# Power.net
KiCad netlist of a schematic drawn in EAGLE
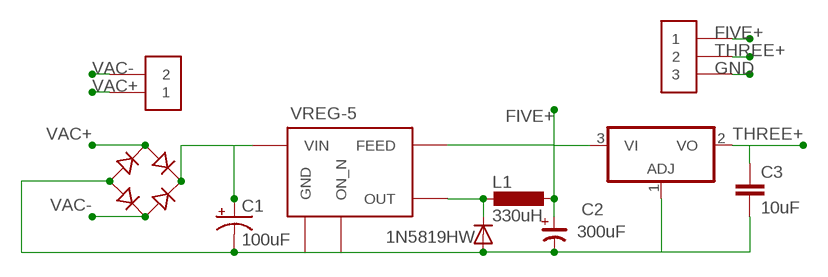
[diagram p0: schematic, sheet 1]

(export (version "E")
  (design (tool "Eeschema 10.0.6"))
  (components
    (comp (ref "B1")
      (value "RECTIFIER-S80")
      (footprint "eagle-import:TO-269AA")
      (libsource (lib "eagle-import") (part "RECTIFIER-S80"))
    )
    (comp (ref "C1")
      (value "100uF")
      (footprint "eagle-import:PANASONIC_G")
      (libsource (lib "eagle-import") (part "CPOL-USG"))
    )
    (comp (ref "C2")
      (value "300uF")
      (footprint "eagle-import:CSV-H")
      (libsource (lib "eagle-import") (part "CP_SV-H"))
    )
    (comp (ref "C3")
      (value "10uF")
      (footprint "eagle-import:C5B2.5")
      (libsource (lib "eagle-import") (part "C5/2.5"))
    )
    (comp (ref "D8")
      (value "CGRM4001-G")
      (footprint "eagle-import:SOD-123_MINI-SMA")
      (libsource (lib "eagle-import") (part "CGRM400-G1"))
    )
    (comp (ref "L1")
      (value "330uH")
      (footprint "eagle-import:DO3316P")
      (libsource (lib "eagle-import") (part "DO3316P"))
    )
    (comp (ref "LT1086-3.3")
      (value "317T")
      (footprint "eagle-import:TO220H")
      (libsource (lib "eagle-import") (part "317T"))
    )
    (comp (ref "U$2")
      (value "OSTTC020162")
      (footprint "eagle-import:OSTTC020162")
      (libsource (lib "eagle-import") (part "OSTTC020162"))
    )
    (comp (ref "U$3")
      (value "OSTTC030162")
      (footprint "eagle-import:OSTTC030162")
      (libsource (lib "eagle-import") (part "OSTTC030162"))
    )
    (comp (ref "VREG-5")
      (value "TL2575-05")
      (footprint "eagle-import:TO-263-5")
      (libsource (lib "eagle-import") (part "TL2575-05"))
    )
  )
  (nets
    (net (code "1") (name "/FIVE+") (class "Default")
      (node (ref "C2") (pin "+") (pinfunction "+_+") (pintype "passive"))
      (node (ref "L1") (pin "2") (pinfunction "2_2") (pintype "passive"))
      (node (ref "LT1086-3.3") (pin "3") (pinfunction "VI_3") (pintype "input"))
      (node (ref "U$3") (pin "1") (pinfunction "1_1") (pintype "bidirectional"))
      (node (ref "VREG-5") (pin "4") (pinfunction "FEED_4") (pintype "bidirectional"))
    )
    (net (code "2") (name "/GND") (class "Default")
      (node (ref "B1") (pin "-") (pinfunction "-_-") (pintype "passive"))
      (node (ref "C1") (pin "-") (pinfunction "-_-") (pintype "passive"))
      (node (ref "C2") (pin "-") (pinfunction "-_-") (pintype "passive"))
      (node (ref "C3") (pin "2") (pinfunction "2_2") (pintype "passive"))
      (node (ref "D8") (pin "A") (pinfunction "A_A") (pintype "passive"))
      (node (ref "LT1086-3.3") (pin "1") (pinfunction "ADJ_1") (pintype "input"))
      (node (ref "U$3") (pin "3") (pinfunction "3_3") (pintype "bidirectional"))
      (node (ref "VREG-5") (pin "3") (pinfunction "GND_3") (pintype "bidirectional"))
      (node (ref "VREG-5") (pin "5") (pinfunction "ON_N_5") (pintype "bidirectional"))
      (node (ref "VREG-5") (pin "TAB") (pinfunction "GND_TAB") (pintype "bidirectional"))
    )
    (net (code "3") (name "/THREE+") (class "Default")
      (node (ref "C3") (pin "1") (pinfunction "1_1") (pintype "passive"))
      (node (ref "LT1086-3.3") (pin "2") (pinfunction "VO_2") (pintype "passive"))
      (node (ref "U$3") (pin "2") (pinfunction "2_2") (pintype "bidirectional"))
    )
    (net (code "4") (name "/VAC+") (class "Default")
      (node (ref "B1") (pin "AC1") (pinfunction "AC1_AC1") (pintype "passive"))
      (node (ref "U$2") (pin "1") (pinfunction "1_1") (pintype "bidirectional"))
    )
    (net (code "5") (name "/VAC-") (class "Default")
      (node (ref "B1") (pin "AC2") (pinfunction "AC2_AC2") (pintype "passive"))
      (node (ref "U$2") (pin "2") (pinfunction "2_2") (pintype "bidirectional"))
    )
    (net (code "6") (name "Net-(VREG-5-OUT)") (class "Default")
      (node (ref "D8") (pin "C") (pinfunction "C_C") (pintype "passive"))
      (node (ref "L1") (pin "1") (pinfunction "1_1") (pintype "passive"))
      (node (ref "VREG-5") (pin "2") (pinfunction "OUT_2") (pintype "bidirectional"))
    )
    (net (code "7") (name "Net-(VREG-5-VIN)") (class "Default")
      (node (ref "B1") (pin "+") (pinfunction "+_+") (pintype "passive"))
      (node (ref "C1") (pin "+") (pinfunction "+_+") (pintype "passive"))
      (node (ref "VREG-5") (pin "1") (pinfunction "VIN_1") (pintype "bidirectional"))
    )
  )
)
